# MCU.net
KiCad netlist of a schematic drawn in Altium Designer
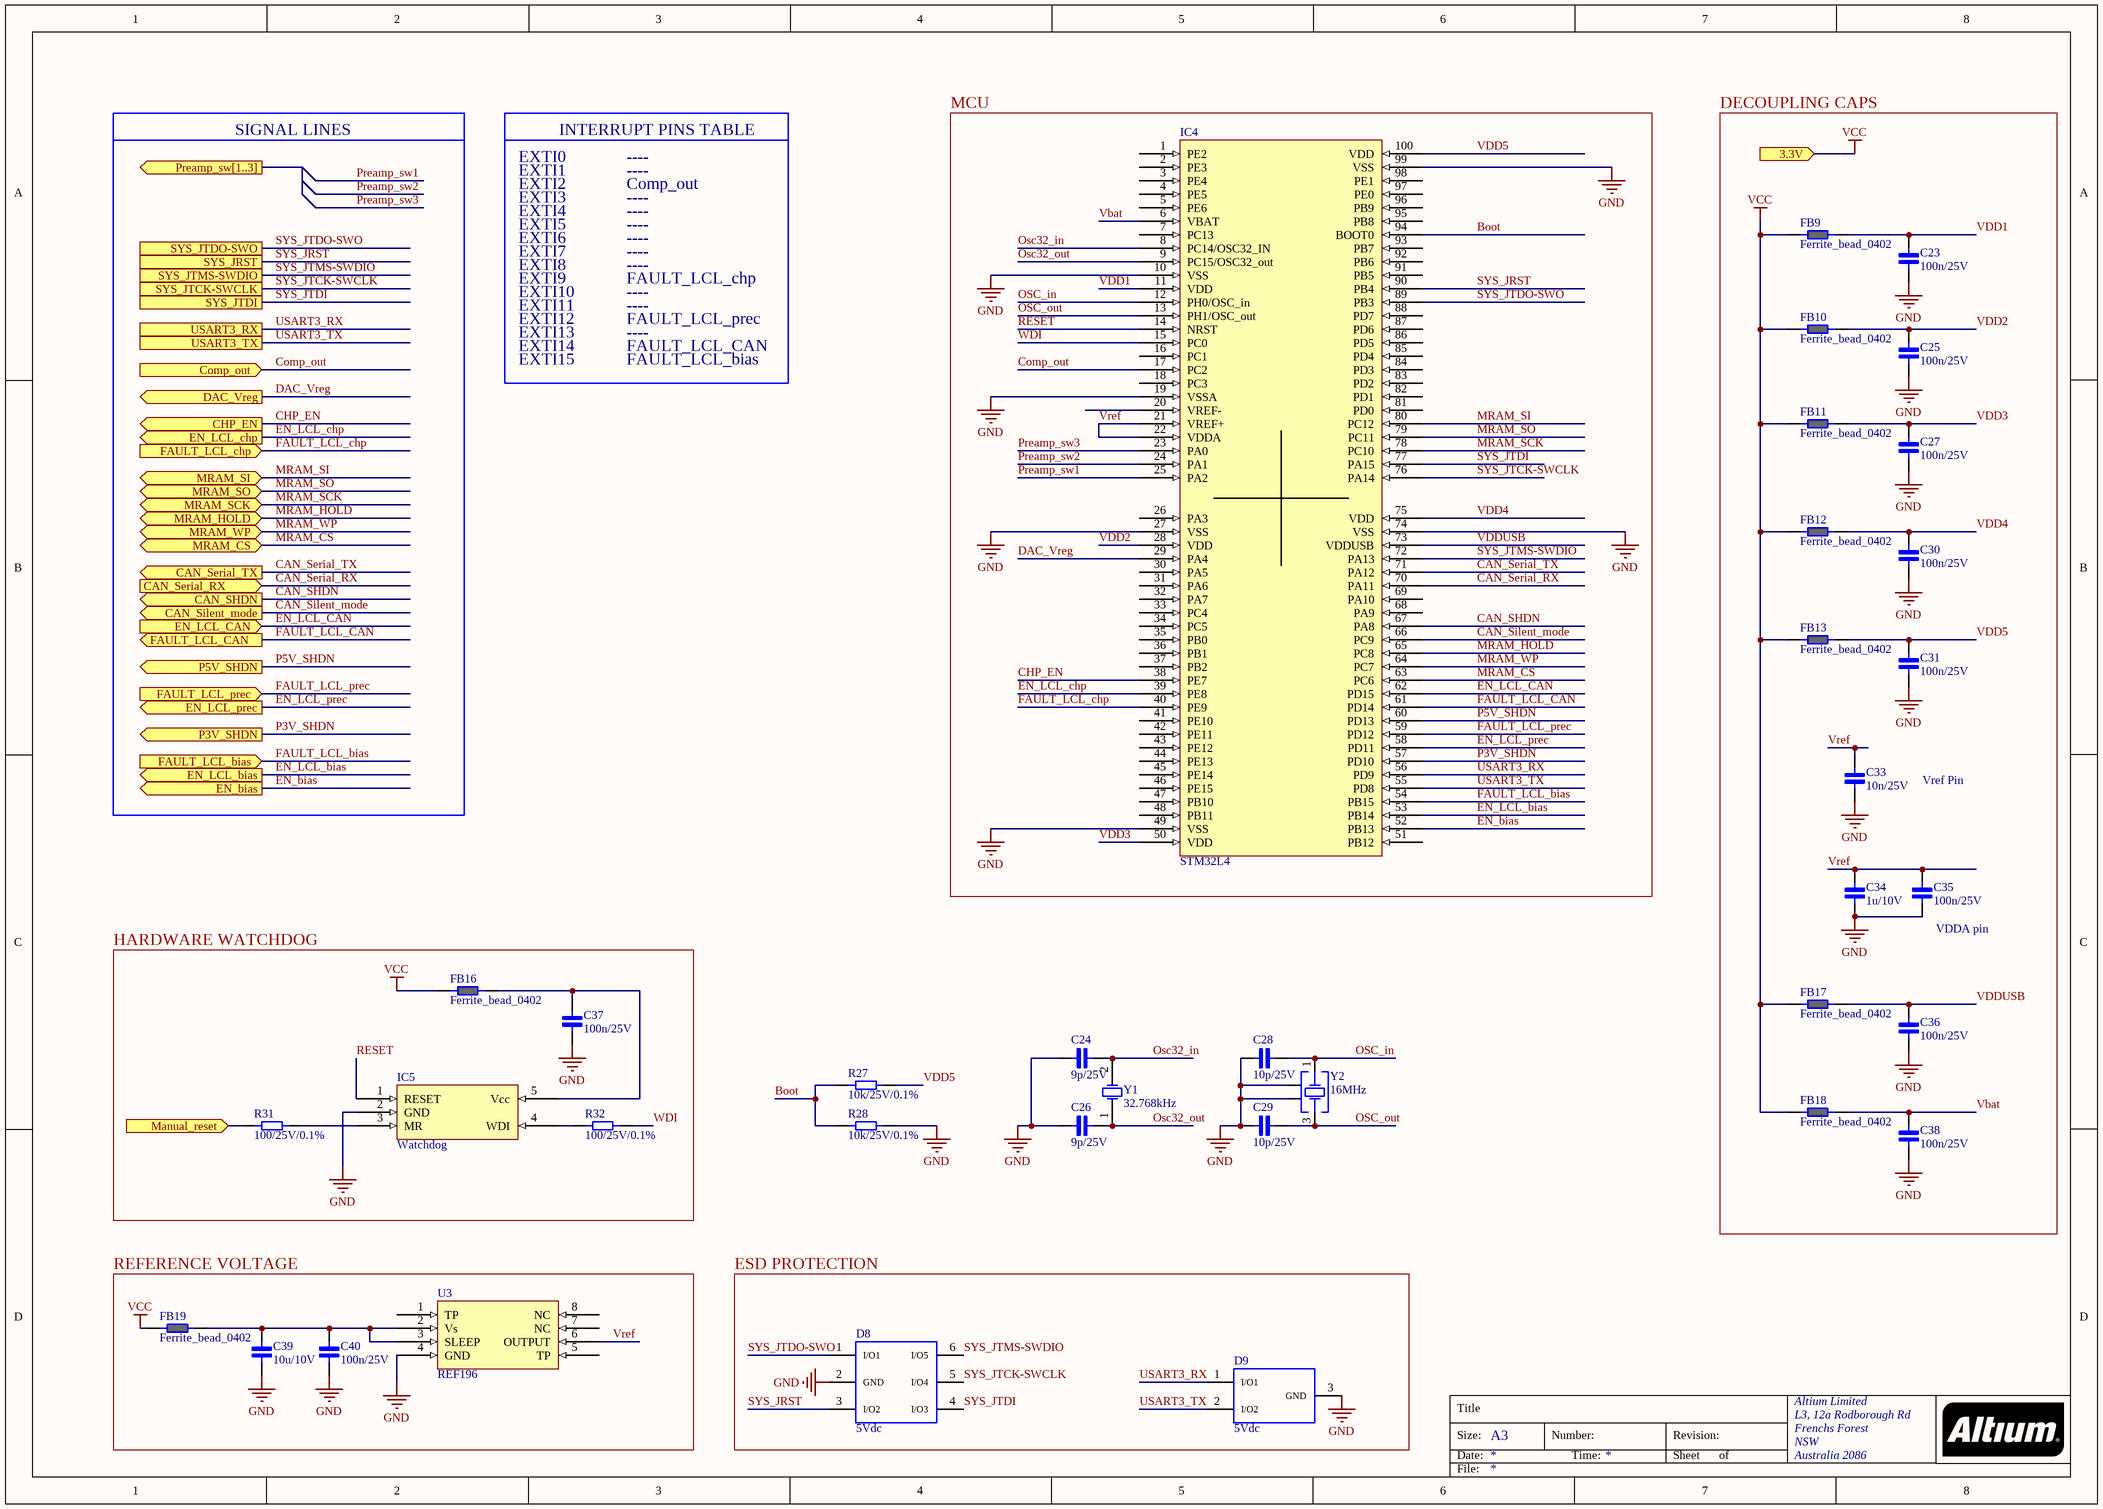
[diagram p0: MCU.SchDoc]

(export (version "E")
  (design (tool "Eeschema 10.0.6"))
  (components
    (comp (ref "C23")
      (value "100n/25V")
      (footprint "Cap_0402")
      (description "Ceramic Capacitor 100n / 0402 / 25V / ±5%, Wurth Elektronik MLCC")
      (libsource (lib "Cubesat_lib") (part "Cap_0402_100n"))
    )
    (comp (ref "C24")
      (value "9p/25V")
      (footprint "Cap_0402")
      (description "0402 / 25V / ±5%, Wurth Elektronik MLCC")
      (libsource (lib "Cubesat_lib") (part "Cap_0402_9p"))
    )
    (comp (ref "C25")
      (value "100n/25V")
      (footprint "Cap_0402")
      (description "Ceramic Capacitor 100n / 0402 / 25V / ±5%, Wurth Elektronik MLCC")
      (libsource (lib "Cubesat_lib") (part "Cap_0402_100n"))
    )
    (comp (ref "C26")
      (value "9p/25V")
      (footprint "Cap_0402")
      (description "0402 / 25V / ±5%, Wurth Elektronik MLCC")
      (libsource (lib "Cubesat_lib") (part "Cap_0402_9p"))
    )
    (comp (ref "C27")
      (value "100n/25V")
      (footprint "Cap_0402")
      (description "Ceramic Capacitor 100n / 0402 / 25V / ±5%, Wurth Elektronik MLCC")
      (libsource (lib "Cubesat_lib") (part "Cap_0402_100n"))
    )
    (comp (ref "C28")
      (value "10p/25V")
      (footprint "Cap_0402")
      (description "0402 / 25V / ±5%, Wurth Elektronik MLCC")
      (libsource (lib "Cubesat_lib") (part "Cap_0402_10p"))
    )
    (comp (ref "C29")
      (value "10p/25V")
      (footprint "Cap_0402")
      (description "0402 / 25V / ±5%, Wurth Elektronik MLCC")
      (libsource (lib "Cubesat_lib") (part "Cap_0402_10p"))
    )
    (comp (ref "C30")
      (value "100n/25V")
      (footprint "Cap_0402")
      (description "Ceramic Capacitor 100n / 0402 / 25V / ±5%, Wurth Elektronik MLCC")
      (libsource (lib "Cubesat_lib") (part "Cap_0402_100n"))
    )
    (comp (ref "C31")
      (value "100n/25V")
      (footprint "Cap_0402")
      (description "Ceramic Capacitor 100n / 0402 / 25V / ±5%, Wurth Elektronik MLCC")
      (libsource (lib "Cubesat_lib") (part "Cap_0402_100n"))
    )
    (comp (ref "C33")
      (value "10n/25V")
      (footprint "Cap_0402")
      (description "Ceramic Capacitor 10n / 0402 / 25V / ±5%, Wurth Elektronik MLCC")
      (libsource (lib "Cubesat_lib") (part "Cap_0402_10n"))
    )
    (comp (ref "C34")
      (value "1u/10V")
      (footprint "Cap_0402")
      (description "Ceramic Capacitor 1uF / 0402 / 10V / ±5%, Wurth Elektronik MLCC")
      (libsource (lib "Cubesat_lib") (part "Cap_0402_1u"))
    )
    (comp (ref "C35")
      (value "100n/25V")
      (footprint "Cap_0402")
      (description "Ceramic Capacitor 100n / 0402 / 25V / ±5%, Wurth Elektronik MLCC")
      (libsource (lib "Cubesat_lib") (part "Cap_0402_100n"))
    )
    (comp (ref "C36")
      (value "100n/25V")
      (footprint "Cap_0402")
      (description "Ceramic Capacitor 100n / 0402 / 25V / ±5%, Wurth Elektronik MLCC")
      (libsource (lib "Cubesat_lib") (part "Cap_0402_100n"))
    )
    (comp (ref "C37")
      (value "100n/25V")
      (footprint "Cap_0402")
      (description "Ceramic Capacitor 100n / 0402 / 25V / ±5%, Wurth Elektronik MLCC")
      (libsource (lib "Cubesat_lib") (part "Cap_0402_100n"))
    )
    (comp (ref "C38")
      (value "100n/25V")
      (footprint "Cap_0402")
      (description "Ceramic Capacitor 100n / 0402 / 25V / ±5%, Wurth Elektronik MLCC")
      (libsource (lib "Cubesat_lib") (part "Cap_0402_100n"))
    )
    (comp (ref "C39")
      (value "10u/10V")
      (footprint "CAP_0603")
      (description "Ceramic Capacitor 10uF / 0603 / 10V / ±5%, Wurth Elektronik MLCC")
      (libsource (lib "Cubesat_lib") (part "Cap_0603_10u"))
    )
    (comp (ref "C40")
      (value "100n/25V")
      (footprint "Cap_0402")
      (description "Ceramic Capacitor 100n / 0402 / 25V / ±5%, Wurth Elektronik MLCC")
      (libsource (lib "Cubesat_lib") (part "Cap_0402_100n"))
    )
    (comp (ref "D8")
      (value "5Vdc")
      (footprint "WE-TVS_SOT23-6L")
      (description "WE-TVS TVS Diode - Standard Series, SOT23-6L, 5Channel, 5Vdc")
      (fields
        (field (name "MANUFACTURER PART NUMBER") "82402305")
        (field (name "MANUFACTURER") "Wurth Elektronik")
      )
      (libsource (lib "WE-TVS_standard_tvs") (part "82402305"))
    )
    (comp (ref "D9")
      (value "5Vdc")
      (footprint "WE-TVS_SOT23-3L")
      (description "WE-TVS TVS Diode - Standard Series, SOT23-3L, 2Channel, 5Vdc")
      (fields
        (field (name "MANUFACTURER PART NUMBER") "824021")
        (field (name "MANUFACTURER") "Wurth Elektronik")
      )
      (libsource (lib "WE-TVS_standard_tvs") (part "824021"))
    )
    (comp (ref "FB9")
      (value "Ferrite_bead_0402")
      (footprint "FERRITE_0402")
      (description "Ferrite bead, wurth 74269241102")
      (libsource (lib "Cubesat_lib") (part "Ferrite_bead_0402"))
    )
    (comp (ref "FB10")
      (value "Ferrite_bead_0402")
      (footprint "FERRITE_0402")
      (description "Ferrite bead, wurth 74269241102")
      (libsource (lib "Cubesat_lib") (part "Ferrite_bead_0402"))
    )
    (comp (ref "FB11")
      (value "Ferrite_bead_0402")
      (footprint "FERRITE_0402")
      (description "Ferrite bead, wurth 74269241102")
      (libsource (lib "Cubesat_lib") (part "Ferrite_bead_0402"))
    )
    (comp (ref "FB12")
      (value "Ferrite_bead_0402")
      (footprint "FERRITE_0402")
      (description "Ferrite bead, wurth 74269241102")
      (libsource (lib "Cubesat_lib") (part "Ferrite_bead_0402"))
    )
    (comp (ref "FB13")
      (value "Ferrite_bead_0402")
      (footprint "FERRITE_0402")
      (description "Ferrite bead, wurth 74269241102")
      (libsource (lib "Cubesat_lib") (part "Ferrite_bead_0402"))
    )
    (comp (ref "FB16")
      (value "Ferrite_bead_0402")
      (footprint "FERRITE_0402")
      (description "Ferrite bead, wurth 74269241102")
      (libsource (lib "Cubesat_lib") (part "Ferrite_bead_0402"))
    )
    (comp (ref "FB17")
      (value "Ferrite_bead_0402")
      (footprint "FERRITE_0402")
      (description "Ferrite bead, wurth 74269241102")
      (libsource (lib "Cubesat_lib") (part "Ferrite_bead_0402"))
    )
    (comp (ref "FB18")
      (value "Ferrite_bead_0402")
      (footprint "FERRITE_0402")
      (description "Ferrite bead, wurth 74269241102")
      (libsource (lib "Cubesat_lib") (part "Ferrite_bead_0402"))
    )
    (comp (ref "FB19")
      (value "Ferrite_bead_0402")
      (footprint "FERRITE_0402")
      (description "Ferrite bead, wurth 74269241102")
      (libsource (lib "Cubesat_lib") (part "Ferrite_bead_0402"))
    )
    (comp (ref "IC4")
      (value "STM32L4")
      (footprint "LQFP100")
      (description "Microcontroller STM32")
      (libsource (lib "Cubesat_lib") (part "STM32L476VGT6"))
    )
    (comp (ref "IC5")
      (value "Watchdog")
      (footprint "SOT-23-5")
      (description "Watchdog, 5-Pin Microprocessor Supervisory Circuits With\r\nWatchdog Timer and Manual Reset")
      (libsource (lib "Cubesat_lib") (part "MAX823"))
    )
    (comp (ref "R27")
      (value "10k/25V/0.1%")
      (footprint "RES_0402")
      (description "Vishay, thin film resistor 10k/25V/0.1%")
      (libsource (lib "Cubesat_lib") (part "Res_0402_10k"))
    )
    (comp (ref "R28")
      (value "10k/25V/0.1%")
      (footprint "RES_0402")
      (description "Vishay, thin film resistor 10k/25V/0.1%")
      (libsource (lib "Cubesat_lib") (part "Res_0402_10k"))
    )
    (comp (ref "R31")
      (value "100/25V/0.1%")
      (footprint "RES_0402")
      (description "Vishay, thin film resistor 100/25V/0.1%")
      (libsource (lib "Cubesat_lib") (part "Res_0402_100"))
    )
    (comp (ref "R32")
      (value "100/25V/0.1%")
      (footprint "RES_0402")
      (description "Vishay, thin film resistor 100/25V/0.1%")
      (libsource (lib "Cubesat_lib") (part "Res_0402_100"))
    )
    (comp (ref "U3")
      (value "REF196")
      (footprint "SOIC8")
      (description "Precision Micropower,\r\nLow Dropout Voltage References")
      (libsource (lib "Cubesat_lib") (part "REF196"))
    )
    (comp (ref "Y1")
      (value "32.768kHz")
      (footprint "WE-XTAL_IQXC-25")
      (description "WE-XTAL Watch Crystal, SMT, IQXC-25, 32.768kHz, +/-10ppm")
      (fields
        (field (name "MANUFACTURER PART NUMBER") "830062558")
        (field (name "MANUFACTURER") "Wurth Elektronik")
      )
      (libsource (lib "32khz_crystal") (part "830062558"))
    )
    (comp (ref "Y2")
      (value "16MHz")
      (footprint "WE-XTAL_CFPX-218")
      (description "WE-XTAL Quartz Crystal, SMT, CFPX-218, 16MHz, +/-20ppm")
      (fields
        (field (name "MANUFACTURER PART NUMBER") "830069392")
        (field (name "MANUFACTURER") "Wurth Elektronik")
      )
      (libsource (lib "HSE_crystal") (part "830069392"))
    )
  )
  (nets
    (net (code "1") (name "/Boot") (class "Default")
      (node (ref "IC4") (pin "94") (pinfunction "BOOT0_94") (pintype "input"))
      (node (ref "R27") (pin "1") (pinfunction "1_1") (pintype "passive"))
      (node (ref "R28") (pin "1") (pinfunction "1_1") (pintype "passive"))
    )
    (net (code "2") (name "/CAN_SHDN") (class "Default")
      (node (ref "IC4") (pin "67") (pinfunction "PA8_67") (pintype "input"))
    )
    (net (code "3") (name "/CAN_Serial_RX") (class "Default")
      (node (ref "IC4") (pin "70") (pinfunction "PA11_70") (pintype "input"))
    )
    (net (code "4") (name "/CAN_Serial_TX") (class "Default")
      (node (ref "IC4") (pin "71") (pinfunction "PA12_71") (pintype "input"))
    )
    (net (code "5") (name "/CAN_Silent_mode") (class "Default")
      (node (ref "IC4") (pin "66") (pinfunction "PC9_66") (pintype "input"))
    )
    (net (code "6") (name "/CHP_EN") (class "Default")
      (node (ref "IC4") (pin "38") (pinfunction "PE7_38") (pintype "input"))
    )
    (net (code "7") (name "/Comp_out") (class "Default")
      (node (ref "IC4") (pin "17") (pinfunction "PC2_17") (pintype "input"))
    )
    (net (code "8") (name "/DAC_Vreg") (class "Default")
      (node (ref "IC4") (pin "29") (pinfunction "PA4_29") (pintype "input"))
    )
    (net (code "9") (name "/EN_LCL_CAN") (class "Default")
      (node (ref "IC4") (pin "62") (pinfunction "PD15_62") (pintype "input"))
    )
    (net (code "10") (name "/EN_LCL_bias") (class "Default")
      (node (ref "IC4") (pin "53") (pinfunction "PB14_53") (pintype "input"))
    )
    (net (code "11") (name "/EN_LCL_chp") (class "Default")
      (node (ref "IC4") (pin "39") (pinfunction "PE8_39") (pintype "input"))
    )
    (net (code "12") (name "/EN_LCL_prec") (class "Default")
      (node (ref "IC4") (pin "58") (pinfunction "PD11_58") (pintype "input"))
    )
    (net (code "13") (name "/EN_bias") (class "Default")
      (node (ref "IC4") (pin "52") (pinfunction "PB13_52") (pintype "input"))
    )
    (net (code "14") (name "/FAULT_LCL_CAN") (class "Default")
      (node (ref "IC4") (pin "61") (pinfunction "PD14_61") (pintype "input"))
    )
    (net (code "15") (name "/FAULT_LCL_bias") (class "Default")
      (node (ref "IC4") (pin "54") (pinfunction "PB15_54") (pintype "input"))
    )
    (net (code "16") (name "/FAULT_LCL_chp") (class "Default")
      (node (ref "IC4") (pin "40") (pinfunction "PE9_40") (pintype "input"))
    )
    (net (code "17") (name "/FAULT_LCL_prec") (class "Default")
      (node (ref "IC4") (pin "59") (pinfunction "PD12_59") (pintype "input"))
    )
    (net (code "18") (name "/MRAM_CS") (class "Default")
      (node (ref "IC4") (pin "63") (pinfunction "PC6_63") (pintype "input"))
    )
    (net (code "19") (name "/MRAM_HOLD") (class "Default")
      (node (ref "IC4") (pin "65") (pinfunction "PC8_65") (pintype "input"))
    )
    (net (code "20") (name "/MRAM_SCK") (class "Default")
      (node (ref "IC4") (pin "78") (pinfunction "PC10_78") (pintype "input"))
    )
    (net (code "21") (name "/MRAM_SI") (class "Default")
      (node (ref "IC4") (pin "80") (pinfunction "PC12_80") (pintype "input"))
    )
    (net (code "22") (name "/MRAM_SO") (class "Default")
      (node (ref "IC4") (pin "79") (pinfunction "PC11_79") (pintype "input"))
    )
    (net (code "23") (name "/MRAM_WP") (class "Default")
      (node (ref "IC4") (pin "64") (pinfunction "PC7_64") (pintype "input"))
    )
    (net (code "24") (name "/Manual_reset") (class "Default")
      (node (ref "R31") (pin "1") (pinfunction "1_1") (pintype "passive"))
    )
    (net (code "25") (name "/OSC_in") (class "Default")
      (node (ref "C28") (pin "2") (pinfunction "2_2") (pintype "passive"))
      (node (ref "IC4") (pin "12") (pinfunction "PH0/OSC_in_12") (pintype "input"))
      (node (ref "Y2") (pin "1") (pinfunction "Crystal_1") (pintype "passive"))
    )
    (net (code "26") (name "/OSC_out") (class "Default")
      (node (ref "C29") (pin "2") (pinfunction "2_2") (pintype "passive"))
      (node (ref "IC4") (pin "13") (pinfunction "PH1/OSC_out_13") (pintype "input"))
      (node (ref "Y2") (pin "3") (pinfunction "Crystal_3") (pintype "passive"))
    )
    (net (code "27") (name "/Osc32_in") (class "Default")
      (node (ref "C24") (pin "2") (pinfunction "2_2") (pintype "passive"))
      (node (ref "IC4") (pin "8") (pinfunction "PC14/OSC32_IN_8") (pintype "input"))
      (node (ref "Y1") (pin "2") (pinfunction "OSC2_2") (pintype "passive"))
    )
    (net (code "28") (name "/Osc32_out") (class "Default")
      (node (ref "C26") (pin "2") (pinfunction "2_2") (pintype "passive"))
      (node (ref "IC4") (pin "9") (pinfunction "PC15/OSC32_out_9") (pintype "input"))
      (node (ref "Y1") (pin "1") (pinfunction "OSC1_1") (pintype "passive"))
    )
    (net (code "29") (name "/P3V_SHDN") (class "Default")
      (node (ref "IC4") (pin "57") (pinfunction "PD10_57") (pintype "input"))
    )
    (net (code "30") (name "/P5V_SHDN") (class "Default")
      (node (ref "IC4") (pin "60") (pinfunction "PD13_60") (pintype "input"))
    )
    (net (code "31") (name "/Preamp_sw1") (class "Default")
      (node (ref "IC4") (pin "25") (pinfunction "PA2_25") (pintype "input"))
    )
    (net (code "32") (name "/Preamp_sw2") (class "Default")
      (node (ref "IC4") (pin "24") (pinfunction "PA1_24") (pintype "input"))
    )
    (net (code "33") (name "/Preamp_sw3") (class "Default")
      (node (ref "IC4") (pin "23") (pinfunction "PA0_23") (pintype "input"))
    )
    (net (code "35") (name "/RESET") (class "Default")
      (node (ref "IC4") (pin "14") (pinfunction "NRST_14") (pintype "input"))
      (node (ref "IC5") (pin "1") (pinfunction "RESET_1") (pintype "input"))
    )
    (net (code "36") (name "/SYS_JRST") (class "Default")
      (node (ref "D8") (pin "3") (pinfunction "I/O2_3") (pintype "passive"))
      (node (ref "IC4") (pin "90") (pinfunction "PB4_90") (pintype "input"))
    )
    (net (code "37") (name "/SYS_JTCK-SWCLK") (class "Default")
      (node (ref "D8") (pin "5") (pinfunction "I/O4_5") (pintype "passive"))
      (node (ref "IC4") (pin "76") (pinfunction "PA14_76") (pintype "input"))
    )
    (net (code "38") (name "/SYS_JTDI") (class "Default")
      (node (ref "D8") (pin "4") (pinfunction "I/O3_4") (pintype "passive"))
      (node (ref "IC4") (pin "77") (pinfunction "PA15_77") (pintype "input"))
    )
    (net (code "39") (name "/SYS_JTDO-SWO") (class "Default")
      (node (ref "D8") (pin "1") (pinfunction "I/O1_1") (pintype "passive"))
      (node (ref "IC4") (pin "89") (pinfunction "PB3_89") (pintype "input"))
    )
    (net (code "40") (name "/SYS_JTMS-SWDIO") (class "Default")
      (node (ref "D8") (pin "6") (pinfunction "I/O5_6") (pintype "passive"))
      (node (ref "IC4") (pin "72") (pinfunction "PA13_72") (pintype "input"))
    )
    (net (code "41") (name "/USART3_RX") (class "Default")
      (node (ref "D9") (pin "1") (pinfunction "I/O1_1") (pintype "passive"))
      (node (ref "IC4") (pin "56") (pinfunction "PD9_56") (pintype "input"))
    )
    (net (code "42") (name "/USART3_TX") (class "Default")
      (node (ref "D9") (pin "2") (pinfunction "I/O2_2") (pintype "passive"))
      (node (ref "IC4") (pin "55") (pinfunction "PD8_55") (pintype "input"))
    )
    (net (code "43") (name "/VDD1") (class "Default")
      (node (ref "C23") (pin "2") (pinfunction "2_2") (pintype "passive"))
      (node (ref "FB9") (pin "2") (pinfunction "2_2") (pintype "passive"))
      (node (ref "IC4") (pin "11") (pinfunction "VDD_11") (pintype "input"))
    )
    (net (code "44") (name "/VDD2") (class "Default")
      (node (ref "C25") (pin "2") (pinfunction "2_2") (pintype "passive"))
      (node (ref "FB10") (pin "2") (pinfunction "2_2") (pintype "passive"))
      (node (ref "IC4") (pin "28") (pinfunction "VDD_28") (pintype "input"))
    )
    (net (code "45") (name "/VDD3") (class "Default")
      (node (ref "C27") (pin "2") (pinfunction "2_2") (pintype "passive"))
      (node (ref "FB11") (pin "2") (pinfunction "2_2") (pintype "passive"))
      (node (ref "IC4") (pin "50") (pinfunction "VDD_50") (pintype "input"))
    )
    (net (code "46") (name "/VDD4") (class "Default")
      (node (ref "C30") (pin "2") (pinfunction "2_2") (pintype "passive"))
      (node (ref "FB12") (pin "2") (pinfunction "2_2") (pintype "passive"))
      (node (ref "IC4") (pin "75") (pinfunction "VDD_75") (pintype "input"))
    )
    (net (code "47") (name "/VDD5") (class "Default")
      (node (ref "C31") (pin "2") (pinfunction "2_2") (pintype "passive"))
      (node (ref "FB13") (pin "2") (pinfunction "2_2") (pintype "passive"))
      (node (ref "IC4") (pin "100") (pinfunction "VDD_100") (pintype "input"))
      (node (ref "R27") (pin "2") (pinfunction "2_2") (pintype "passive"))
    )
    (net (code "48") (name "/VDDUSB") (class "Default")
      (node (ref "C36") (pin "2") (pinfunction "2_2") (pintype "passive"))
      (node (ref "FB17") (pin "2") (pinfunction "2_2") (pintype "passive"))
      (node (ref "IC4") (pin "73") (pinfunction "VDDUSB_73") (pintype "input"))
    )
    (net (code "49") (name "/Vbat") (class "Default")
      (node (ref "C38") (pin "2") (pinfunction "2_2") (pintype "passive"))
      (node (ref "FB18") (pin "2") (pinfunction "2_2") (pintype "passive"))
      (node (ref "IC4") (pin "6") (pinfunction "VBAT_6") (pintype "input"))
    )
    (net (code "50") (name "/Vref") (class "Default")
      (node (ref "C33") (pin "2") (pinfunction "2_2") (pintype "passive"))
      (node (ref "C34") (pin "2") (pinfunction "2_2") (pintype "passive"))
      (node (ref "C35") (pin "2") (pinfunction "2_2") (pintype "passive"))
      (node (ref "IC4") (pin "21") (pinfunction "VREF+_21") (pintype "input"))
      (node (ref "IC4") (pin "22") (pinfunction "VDDA_22") (pintype "input"))
      (node (ref "U3") (pin "6") (pinfunction "OUTPUT_6") (pintype "input"))
    )
    (net (code "51") (name "/WDI") (class "Default")
      (node (ref "IC4") (pin "15") (pinfunction "PC0_15") (pintype "input"))
      (node (ref "R32") (pin "2") (pinfunction "2_2") (pintype "passive"))
    )
    (net (code "52") (name "GND") (class "Default")
      (node (ref "C23") (pin "1") (pinfunction "1_1") (pintype "passive"))
      (node (ref "C24") (pin "1") (pinfunction "1_1") (pintype "passive"))
      (node (ref "C25") (pin "1") (pinfunction "1_1") (pintype "passive"))
      (node (ref "C26") (pin "1") (pinfunction "1_1") (pintype "passive"))
      (node (ref "C27") (pin "1") (pinfunction "1_1") (pintype "passive"))
      (node (ref "C28") (pin "1") (pinfunction "1_1") (pintype "passive"))
      (node (ref "C29") (pin "1") (pinfunction "1_1") (pintype "passive"))
      (node (ref "C30") (pin "1") (pinfunction "1_1") (pintype "passive"))
      (node (ref "C31") (pin "1") (pinfunction "1_1") (pintype "passive"))
      (node (ref "C33") (pin "1") (pinfunction "1_1") (pintype "passive"))
      (node (ref "C34") (pin "1") (pinfunction "1_1") (pintype "passive"))
      (node (ref "C35") (pin "1") (pinfunction "1_1") (pintype "passive"))
      (node (ref "C36") (pin "1") (pinfunction "1_1") (pintype "passive"))
      (node (ref "C37") (pin "1") (pinfunction "1_1") (pintype "passive"))
      (node (ref "C38") (pin "1") (pinfunction "1_1") (pintype "passive"))
      (node (ref "C39") (pin "1") (pinfunction "1_1") (pintype "passive"))
      (node (ref "C40") (pin "1") (pinfunction "1_1") (pintype "passive"))
      (node (ref "D8") (pin "2") (pinfunction "GND_2") (pintype "passive"))
      (node (ref "D9") (pin "3") (pinfunction "GND_3") (pintype "passive"))
      (node (ref "IC4") (pin "10") (pinfunction "VSS_10") (pintype "input"))
      (node (ref "IC4") (pin "19") (pinfunction "VSSA_19") (pintype "input"))
      (node (ref "IC4") (pin "27") (pinfunction "VSS_27") (pintype "input"))
      (node (ref "IC4") (pin "49") (pinfunction "VSS_49") (pintype "input"))
      (node (ref "IC4") (pin "74") (pinfunction "VSS_74") (pintype "input"))
      (node (ref "IC4") (pin "99") (pinfunction "VSS_99") (pintype "input"))
      (node (ref "IC5") (pin "2") (pinfunction "GND_2") (pintype "input"))
      (node (ref "R28") (pin "2") (pinfunction "2_2") (pintype "passive"))
      (node (ref "U3") (pin "4") (pinfunction "GND_4") (pintype "input"))
      (node (ref "Y2") (pin "2") (pinfunction "GND_2") (pintype "passive"))
      (node (ref "Y2") (pin "4") (pinfunction "GND_4") (pintype "passive"))
    )
    (net (code "53") (name "Net-(IC5-MR)") (class "Default")
      (node (ref "IC5") (pin "3") (pinfunction "MR_3") (pintype "input"))
      (node (ref "R31") (pin "2") (pinfunction "2_2") (pintype "passive"))
    )
    (net (code "54") (name "Net-(IC5-Vcc)") (class "Default")
      (node (ref "C37") (pin "2") (pinfunction "2_2") (pintype "passive"))
      (node (ref "FB16") (pin "2") (pinfunction "2_2") (pintype "passive"))
      (node (ref "IC5") (pin "5") (pinfunction "Vcc_5") (pintype "input"))
    )
    (net (code "55") (name "Net-(IC5-WDI)") (class "Default")
      (node (ref "IC5") (pin "4") (pinfunction "WDI_4") (pintype "input"))
      (node (ref "R32") (pin "1") (pinfunction "1_1") (pintype "passive"))
    )
    (net (code "56") (name "Net-(U3-SLEEP)") (class "Default")
      (node (ref "C39") (pin "2") (pinfunction "2_2") (pintype "passive"))
      (node (ref "C40") (pin "2") (pinfunction "2_2") (pintype "passive"))
      (node (ref "FB19") (pin "2") (pinfunction "2_2") (pintype "passive"))
      (node (ref "U3") (pin "2") (pinfunction "Vs_2") (pintype "input"))
      (node (ref "U3") (pin "3") (pinfunction "SLEEP_3") (pintype "input"))
    )
    (net (code "57") (name "VCC") (class "Default")
      (node (ref "FB10") (pin "1") (pinfunction "1_1") (pintype "passive"))
      (node (ref "FB11") (pin "1") (pinfunction "1_1") (pintype "passive"))
      (node (ref "FB12") (pin "1") (pinfunction "1_1") (pintype "passive"))
      (node (ref "FB13") (pin "1") (pinfunction "1_1") (pintype "passive"))
      (node (ref "FB16") (pin "1") (pinfunction "1_1") (pintype "passive"))
      (node (ref "FB17") (pin "1") (pinfunction "1_1") (pintype "passive"))
      (node (ref "FB18") (pin "1") (pinfunction "1_1") (pintype "passive"))
      (node (ref "FB19") (pin "1") (pinfunction "1_1") (pintype "passive"))
      (node (ref "FB9") (pin "1") (pinfunction "1_1") (pintype "passive"))
    )
    (net (code "58") (name "unconnected-(IC4-PA3-Pad26)") (class "Default")
      (node (ref "IC4") (pin "26") (pinfunction "PA3_26") (pintype "input"))
    )
    (net (code "59") (name "unconnected-(IC4-PA5-Pad30)") (class "Default")
      (node (ref "IC4") (pin "30") (pinfunction "PA5_30") (pintype "input"))
    )
    (net (code "60") (name "unconnected-(IC4-PA6-Pad31)") (class "Default")
      (node (ref "IC4") (pin "31") (pinfunction "PA6_31") (pintype "input"))
    )
    (net (code "61") (name "unconnected-(IC4-PA7-Pad32)") (class "Default")
      (node (ref "IC4") (pin "32") (pinfunction "PA7_32") (pintype "input"))
    )
    (net (code "62") (name "unconnected-(IC4-PA9-Pad68)") (class "Default")
      (node (ref "IC4") (pin "68") (pinfunction "PA9_68") (pintype "input"))
    )
    (net (code "63") (name "unconnected-(IC4-PA10-Pad69)") (class "Default")
      (node (ref "IC4") (pin "69") (pinfunction "PA10_69") (pintype "input"))
    )
    (net (code "64") (name "unconnected-(IC4-PB0-Pad35)") (class "Default")
      (node (ref "IC4") (pin "35") (pinfunction "PB0_35") (pintype "input"))
    )
    (net (code "65") (name "unconnected-(IC4-PB1-Pad36)") (class "Default")
      (node (ref "IC4") (pin "36") (pinfunction "PB1_36") (pintype "input"))
    )
    (net (code "66") (name "unconnected-(IC4-PB2-Pad37)") (class "Default")
      (node (ref "IC4") (pin "37") (pinfunction "PB2_37") (pintype "input"))
    )
    (net (code "67") (name "unconnected-(IC4-PB5-Pad91)") (class "Default")
      (node (ref "IC4") (pin "91") (pinfunction "PB5_91") (pintype "input"))
    )
    (net (code "68") (name "unconnected-(IC4-PB6-Pad92)") (class "Default")
      (node (ref "IC4") (pin "92") (pinfunction "PB6_92") (pintype "input"))
    )
    (net (code "69") (name "unconnected-(IC4-PB7-Pad93)") (class "Default")
      (node (ref "IC4") (pin "93") (pinfunction "PB7_93") (pintype "input"))
    )
    (net (code "70") (name "unconnected-(IC4-PB8-Pad95)") (class "Default")
      (node (ref "IC4") (pin "95") (pinfunction "PB8_95") (pintype "input"))
    )
    (net (code "71") (name "unconnected-(IC4-PB9-Pad96)") (class "Default")
      (node (ref "IC4") (pin "96") (pinfunction "PB9_96") (pintype "input"))
    )
    (net (code "72") (name "unconnected-(IC4-PB10-Pad47)") (class "Default")
      (node (ref "IC4") (pin "47") (pinfunction "PB10_47") (pintype "input"))
    )
    (net (code "73") (name "unconnected-(IC4-PB11-Pad48)") (class "Default")
      (node (ref "IC4") (pin "48") (pinfunction "PB11_48") (pintype "input"))
    )
    (net (code "74") (name "unconnected-(IC4-PB12-Pad51)") (class "Default")
      (node (ref "IC4") (pin "51") (pinfunction "PB12_51") (pintype "input"))
    )
    (net (code "75") (name "unconnected-(IC4-PC1-Pad16)") (class "Default")
      (node (ref "IC4") (pin "16") (pinfunction "PC1_16") (pintype "input"))
    )
    (net (code "76") (name "unconnected-(IC4-PC3-Pad18)") (class "Default")
      (node (ref "IC4") (pin "18") (pinfunction "PC3_18") (pintype "input"))
    )
    (net (code "77") (name "unconnected-(IC4-PC4-Pad33)") (class "Default")
      (node (ref "IC4") (pin "33") (pinfunction "PC4_33") (pintype "input"))
    )
    (net (code "78") (name "unconnected-(IC4-PC5-Pad34)") (class "Default")
      (node (ref "IC4") (pin "34") (pinfunction "PC5_34") (pintype "input"))
    )
    (net (code "79") (name "unconnected-(IC4-PC13-Pad7)") (class "Default")
      (node (ref "IC4") (pin "7") (pinfunction "PC13_7") (pintype "input"))
    )
    (net (code "80") (name "unconnected-(IC4-PD0-Pad81)") (class "Default")
      (node (ref "IC4") (pin "81") (pinfunction "PD0_81") (pintype "input"))
    )
    (net (code "81") (name "unconnected-(IC4-PD1-Pad82)") (class "Default")
      (node (ref "IC4") (pin "82") (pinfunction "PD1_82") (pintype "input"))
    )
    (net (code "82") (name "unconnected-(IC4-PD2-Pad83)") (class "Default")
      (node (ref "IC4") (pin "83") (pinfunction "PD2_83") (pintype "input"))
    )
    (net (code "83") (name "unconnected-(IC4-PD3-Pad84)") (class "Default")
      (node (ref "IC4") (pin "84") (pinfunction "PD3_84") (pintype "input"))
    )
    (net (code "84") (name "unconnected-(IC4-PD4-Pad85)") (class "Default")
      (node (ref "IC4") (pin "85") (pinfunction "PD4_85") (pintype "input"))
    )
    (net (code "85") (name "unconnected-(IC4-PD5-Pad86)") (class "Default")
      (node (ref "IC4") (pin "86") (pinfunction "PD5_86") (pintype "input"))
    )
    (net (code "86") (name "unconnected-(IC4-PD6-Pad87)") (class "Default")
      (node (ref "IC4") (pin "87") (pinfunction "PD6_87") (pintype "input"))
    )
    (net (code "87") (name "unconnected-(IC4-PD7-Pad88)") (class "Default")
      (node (ref "IC4") (pin "88") (pinfunction "PD7_88") (pintype "input"))
    )
    (net (code "88") (name "unconnected-(IC4-PE0-Pad97)") (class "Default")
      (node (ref "IC4") (pin "97") (pinfunction "PE0_97") (pintype "input"))
    )
    (net (code "89") (name "unconnected-(IC4-PE1-Pad98)") (class "Default")
      (node (ref "IC4") (pin "98") (pinfunction "PE1_98") (pintype "input"))
    )
    (net (code "90") (name "unconnected-(IC4-PE2-Pad1)") (class "Default")
      (node (ref "IC4") (pin "1") (pinfunction "PE2_1") (pintype "input"))
    )
    (net (code "91") (name "unconnected-(IC4-PE3-Pad2)") (class "Default")
      (node (ref "IC4") (pin "2") (pinfunction "PE3_2") (pintype "input"))
    )
    (net (code "92") (name "unconnected-(IC4-PE4-Pad3)") (class "Default")
      (node (ref "IC4") (pin "3") (pinfunction "PE4_3") (pintype "input"))
    )
    (net (code "93") (name "unconnected-(IC4-PE5-Pad4)") (class "Default")
      (node (ref "IC4") (pin "4") (pinfunction "PE5_4") (pintype "input"))
    )
    (net (code "94") (name "unconnected-(IC4-PE6-Pad5)") (class "Default")
      (node (ref "IC4") (pin "5") (pinfunction "PE6_5") (pintype "input"))
    )
    (net (code "95") (name "unconnected-(IC4-PE10-Pad41)") (class "Default")
      (node (ref "IC4") (pin "41") (pinfunction "PE10_41") (pintype "input"))
    )
    (net (code "96") (name "unconnected-(IC4-PE11-Pad42)") (class "Default")
      (node (ref "IC4") (pin "42") (pinfunction "PE11_42") (pintype "input"))
    )
    (net (code "97") (name "unconnected-(IC4-PE12-Pad43)") (class "Default")
      (node (ref "IC4") (pin "43") (pinfunction "PE12_43") (pintype "input"))
    )
    (net (code "98") (name "unconnected-(IC4-PE13-Pad44)") (class "Default")
      (node (ref "IC4") (pin "44") (pinfunction "PE13_44") (pintype "input"))
    )
    (net (code "99") (name "unconnected-(IC4-PE14-Pad45)") (class "Default")
      (node (ref "IC4") (pin "45") (pinfunction "PE14_45") (pintype "input"))
    )
    (net (code "100") (name "unconnected-(IC4-PE15-Pad46)") (class "Default")
      (node (ref "IC4") (pin "46") (pinfunction "PE15_46") (pintype "input"))
    )
    (net (code "101") (name "unconnected-(IC4-VREF--Pad20)") (class "Default")
      (node (ref "IC4") (pin "20") (pinfunction "VREF-_20") (pintype "input"))
    )
    (net (code "102") (name "unconnected-(U3-NC-Pad7)") (class "Default")
      (node (ref "U3") (pin "7") (pinfunction "NC_7") (pintype "input"))
    )
    (net (code "103") (name "unconnected-(U3-NC-Pad8)") (class "Default")
      (node (ref "U3") (pin "8") (pinfunction "NC_8") (pintype "input"))
    )
    (net (code "104") (name "unconnected-(U3-TP-Pad1)") (class "Default")
      (node (ref "U3") (pin "1") (pinfunction "TP_1") (pintype "input"))
    )
    (net (code "105") (name "unconnected-(U3-TP-Pad5)") (class "Default")
      (node (ref "U3") (pin "5") (pinfunction "TP_5") (pintype "input"))
    )
  )
)
